# Stm32F411CEU6_Property.net
KiCad netlist of a schematic drawn in Altium Designer
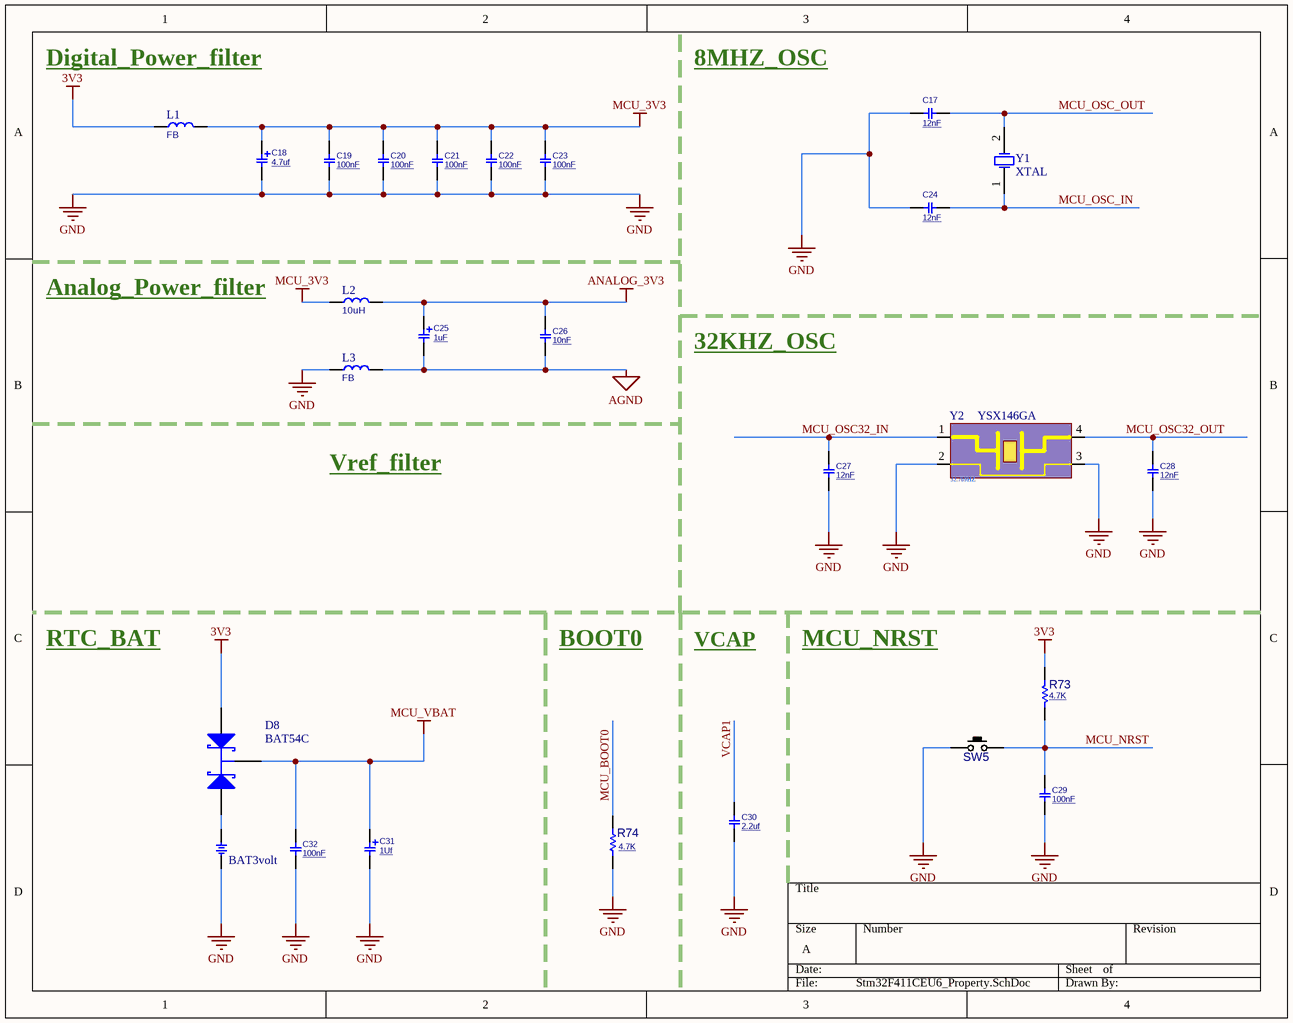
[diagram p0: Stm32F411CEU6_Property.SchDoc]

(export (version "E")
  (design (tool "Eeschema 10.0.6"))
  (components
    (comp (ref "BT1")
      (value "BAT3volt")
      (footprint "BTH1220")
      (description "BATTERY HOLDER, CR1220")
      (libsource (lib "battery") (part "BATH_CR1220"))
    )
    (comp (ref "C17")
      (value "12nF")
      (footprint "C0603")
      (description "CAP, MLCC, -F, -V, MATERIAL, -%, 0201")
      (fields (field (name "MANF_P#") "MANF_PART#"))
      (libsource (lib "passive_smd") (part "CAP_SMD_MLCC_0603"))
    )
    (comp (ref "C18")
      (value "4.7uf")
      (footprint "C_TN_3216")
      (description "CAP, SMD, TAN,")
      (fields (field (name "Comment") "4.7uF"))
      (libsource (lib "passive_smd") (part "CAP_SMD_TAN_3216"))
    )
    (comp (ref "C19")
      (value "100nF")
      (footprint "C0603")
      (description "CAP, MLCC, -F, -V, MATERIAL, -%, 0201")
      (fields (field (name "MANF_P#") "MANF_PART#"))
      (libsource (lib "passive_smd") (part "CAP_SMD_MLCC_0603"))
    )
    (comp (ref "C20")
      (value "100nF")
      (footprint "C0603")
      (description "CAP, MLCC, -F, -V, MATERIAL, -%, 0201")
      (fields (field (name "MANF_P#") "MANF_PART#"))
      (libsource (lib "passive_smd") (part "CAP_SMD_MLCC_0603"))
    )
    (comp (ref "C21")
      (value "100nF")
      (footprint "C0603")
      (description "CAP, MLCC, -F, -V, MATERIAL, -%, 0201")
      (fields (field (name "MANF_P#") "MANF_PART#"))
      (libsource (lib "passive_smd") (part "CAP_SMD_MLCC_0603"))
    )
    (comp (ref "C22")
      (value "100nF")
      (footprint "C0603")
      (description "CAP, MLCC, -F, -V, MATERIAL, -%, 0201")
      (fields (field (name "MANF_P#") "MANF_PART#"))
      (libsource (lib "passive_smd") (part "CAP_SMD_MLCC_0603"))
    )
    (comp (ref "C23")
      (value "100nF")
      (footprint "C0603")
      (description "CAP, MLCC, -F, -V, MATERIAL, -%, 0201")
      (fields (field (name "MANF_P#") "MANF_PART#"))
      (libsource (lib "passive_smd") (part "CAP_SMD_MLCC_0603"))
    )
    (comp (ref "C24")
      (value "12nF")
      (footprint "C0603")
      (description "CAP, MLCC, -F, -V, MATERIAL, -%, 0201")
      (fields (field (name "MANF_P#") "MANF_PART#"))
      (libsource (lib "passive_smd") (part "CAP_SMD_MLCC_0603"))
    )
    (comp (ref "C25")
      (value "1uF")
      (footprint "C_TN_3216")
      (description "CAP, SMD, TAN,")
      (fields (field (name "Comment") "4.7uF"))
      (libsource (lib "passive_smd") (part "CAP_SMD_TAN_3216"))
    )
    (comp (ref "C26")
      (value "10nF")
      (footprint "C0603")
      (description "CAP, MLCC, -F, -V, MATERIAL, -%, 0201")
      (fields (field (name "MANF_P#") "MANF_PART#"))
      (libsource (lib "passive_smd") (part "CAP_SMD_MLCC_0603"))
    )
    (comp (ref "C27")
      (value "12nF")
      (footprint "C0603")
      (description "CAP, MLCC, -F, -V, MATERIAL, -%, 0201")
      (fields (field (name "MANF_P#") "MANF_PART#"))
      (libsource (lib "passive_smd") (part "CAP_SMD_MLCC_0603"))
    )
    (comp (ref "C28")
      (value "12nF")
      (footprint "C0603")
      (description "CAP, MLCC, -F, -V, MATERIAL, -%, 0201")
      (fields (field (name "MANF_P#") "MANF_PART#"))
      (libsource (lib "passive_smd") (part "CAP_SMD_MLCC_0603"))
    )
    (comp (ref "C29")
      (value "100nF")
      (footprint "C0603")
      (description "CAP, MLCC, -F, -V, MATERIAL, -%, 0201")
      (fields (field (name "MANF_P#") "MANF_PART#"))
      (libsource (lib "passive_smd") (part "CAP_SMD_MLCC_0603"))
    )
    (comp (ref "C30")
      (value "2.2uf")
      (footprint "C0603")
      (description "CAP, MLCC, -F, -V, MATERIAL, -%, 0201")
      (fields (field (name "MANF_P#") "MANF_PART#"))
      (libsource (lib "passive_smd") (part "CAP_SMD_MLCC_0603"))
    )
    (comp (ref "C31")
      (value "1Uf")
      (footprint "C_TN_3216")
      (description "CAP, SMD, TAN,")
      (fields (field (name "Comment") "4.7uF"))
      (libsource (lib "passive_smd") (part "CAP_SMD_TAN_3216"))
    )
    (comp (ref "C32")
      (value "100nF")
      (footprint "C0603")
      (description "CAP, MLCC, -F, -V, MATERIAL, -%, 0201")
      (fields (field (name "MANF_P#") "MANF_PART#"))
      (libsource (lib "passive_smd") (part "CAP_SMD_MLCC_0603"))
    )
    (comp (ref "D8")
      (value "BAT54C")
      (footprint "NXP-SOT23-3_V")
      (description "Schottky Barrier Diode, 30 V, 2 uA, -55 to 150 degC, 3-Pin SOT23, RoHS, Tape and Reel")
      (fields (field (name "MANUFACTURER") "NXP Semiconductors"))
      (libsource (lib "BAT54C") (part "CMP-0417-00003-1"))
    )
    (comp (ref "L1")
      (value "FB")
      (footprint "L0805")
      (description "INDUCTOR, SMD")
      (libsource (lib "passive_smd") (part "IND_SMD"))
    )
    (comp (ref "L2")
      (value "10uH")
      (footprint "L1210A")
      (description "INDUCTOR, SMD")
      (libsource (lib "passive_smd") (part "IND_SMD"))
    )
    (comp (ref "L3")
      (value "FB")
      (footprint "L0805")
      (description "INDUCTOR, SMD")
      (libsource (lib "passive_smd") (part "IND_SMD"))
    )
    (comp (ref "R73")
      (value "4.7K")
      (footprint "R0603")
      (description "RESISTOR, SMD")
      (libsource (lib "passive_smd") (part "RES_SMD"))
    )
    (comp (ref "R74")
      (value "4.7K")
      (footprint "R0603")
      (description "RESISTOR, SMD")
      (libsource (lib "passive_smd") (part "RES_SMD"))
    )
    (comp (ref "SW5")
      (value "PUSHBUTTON")
      (footprint "SWPBS_SPST_6X3X5")
      (description "SWITCH, PUSH BUTTON, TACTILE, SMD, SPST, 6X3.5X5mm")
      (fields (field (name "MANF") "ALPS") (field (name "MANF_P#") "SKQMBBE010"))
      (libsource (lib "switch_tact_PUSHB") (part "SWPBS_SPST_6X3X5"))
    )
    (comp (ref "Y1")
      (value "XTAL")
      (footprint "XTL_2_5032")
      (description "Crystal Oscillator")
      (fields (field (name "PUBLISHER") "Altium Limited"))
      (libsource (lib "Miscellaneous Devices") (part "XTAL"))
    )
    (comp (ref "Y2")
      (value "YSX146GA")
      (footprint "YSX146GA-32.768xTAL")
      (libsource (lib "YSX146GA-32.768HZ") (part "YSX146GA"))
    )
  )
  (nets
    (net (code "1") (name "/MCU_BOOT0") (class "Default")
      (node (ref "R74") (pin "2") (pinfunction "2_2") (pintype "passive"))
    )
    (net (code "2") (name "/MCU_NRST") (class "Default")
      (node (ref "C29") (pin "2") (pinfunction "2_2") (pintype "passive"))
      (node (ref "R73") (pin "1") (pinfunction "1_1") (pintype "passive"))
      (node (ref "SW5") (pin "2") (pinfunction "P3_2") (pintype "passive"))
    )
    (net (code "3") (name "/MCU_OSC32_IN") (class "Default")
      (node (ref "C27") (pin "1") (pinfunction "1_1") (pintype "passive"))
      (node (ref "Y2") (pin "1") (pinfunction "1_1") (pintype "passive"))
    )
    (net (code "4") (name "/MCU_OSC32_OUT") (class "Default")
      (node (ref "C28") (pin "1") (pinfunction "1_1") (pintype "passive"))
      (node (ref "Y2") (pin "4") (pinfunction "4_4") (pintype "passive"))
    )
    (net (code "5") (name "/MCU_OSC_IN") (class "Default")
      (node (ref "C24") (pin "1") (pinfunction "1_1") (pintype "passive"))
      (node (ref "Y1") (pin "1") (pinfunction "OSC1_1") (pintype "passive"))
    )
    (net (code "6") (name "/MCU_OSC_OUT") (class "Default")
      (node (ref "C17") (pin "1") (pinfunction "1_1") (pintype "passive"))
      (node (ref "Y1") (pin "2") (pinfunction "OSC2_2") (pintype "passive"))
    )
    (net (code "7") (name "/VCAP1") (class "Default")
      (node (ref "C30") (pin "2") (pinfunction "2_2") (pintype "passive"))
    )
    (net (code "8") (name "3V3") (class "Default")
      (node (ref "D8") (pin "1") (pinfunction "A_1") (pintype "passive"))
      (node (ref "L1") (pin "1") (pinfunction "1_1") (pintype "passive"))
      (node (ref "R73") (pin "2") (pinfunction "2_2") (pintype "passive"))
    )
    (net (code "9") (name "AGND") (class "Default")
      (node (ref "C25") (pin "2") (pinfunction "2_2") (pintype "passive"))
      (node (ref "C26") (pin "1") (pinfunction "1_1") (pintype "passive"))
      (node (ref "L3") (pin "2") (pinfunction "2_2") (pintype "passive"))
    )
    (net (code "10") (name "ANALOG_3V3") (class "Default")
      (node (ref "C25") (pin "1") (pinfunction "1_1") (pintype "passive"))
      (node (ref "C26") (pin "2") (pinfunction "2_2") (pintype "passive"))
      (node (ref "L2") (pin "2") (pinfunction "2_2") (pintype "passive"))
    )
    (net (code "11") (name "GND") (class "Default")
      (node (ref "BT1") (pin "2") (pinfunction "2_2") (pintype "passive"))
      (node (ref "C17") (pin "2") (pinfunction "2_2") (pintype "passive"))
      (node (ref "C18") (pin "2") (pinfunction "2_2") (pintype "passive"))
      (node (ref "C19") (pin "1") (pinfunction "1_1") (pintype "passive"))
      (node (ref "C20") (pin "1") (pinfunction "1_1") (pintype "passive"))
      (node (ref "C21") (pin "1") (pinfunction "1_1") (pintype "passive"))
      (node (ref "C22") (pin "1") (pinfunction "1_1") (pintype "passive"))
      (node (ref "C23") (pin "1") (pinfunction "1_1") (pintype "passive"))
      (node (ref "C24") (pin "2") (pinfunction "2_2") (pintype "passive"))
      (node (ref "C27") (pin "2") (pinfunction "2_2") (pintype "passive"))
      (node (ref "C28") (pin "2") (pinfunction "2_2") (pintype "passive"))
      (node (ref "C29") (pin "1") (pinfunction "1_1") (pintype "passive"))
      (node (ref "C30") (pin "1") (pinfunction "1_1") (pintype "passive"))
      (node (ref "C31") (pin "2") (pinfunction "2_2") (pintype "passive"))
      (node (ref "C32") (pin "1") (pinfunction "1_1") (pintype "passive"))
      (node (ref "L3") (pin "1") (pinfunction "1_1") (pintype "passive"))
      (node (ref "R74") (pin "1") (pinfunction "1_1") (pintype "passive"))
      (node (ref "SW5") (pin "1") (pinfunction "P1_1") (pintype "passive"))
      (node (ref "Y2") (pin "2") (pinfunction "2_2") (pintype "passive"))
      (node (ref "Y2") (pin "3") (pinfunction "3_3") (pintype "passive"))
    )
    (net (code "12") (name "MCU_3V3") (class "Default")
      (node (ref "C18") (pin "1") (pinfunction "1_1") (pintype "passive"))
      (node (ref "C19") (pin "2") (pinfunction "2_2") (pintype "passive"))
      (node (ref "C20") (pin "2") (pinfunction "2_2") (pintype "passive"))
      (node (ref "C21") (pin "2") (pinfunction "2_2") (pintype "passive"))
      (node (ref "C22") (pin "2") (pinfunction "2_2") (pintype "passive"))
      (node (ref "C23") (pin "2") (pinfunction "2_2") (pintype "passive"))
      (node (ref "L1") (pin "2") (pinfunction "2_2") (pintype "passive"))
      (node (ref "L2") (pin "1") (pinfunction "1_1") (pintype "passive"))
    )
    (net (code "13") (name "MCU_VBAT") (class "Default")
      (node (ref "C31") (pin "1") (pinfunction "1_1") (pintype "passive"))
      (node (ref "C32") (pin "2") (pinfunction "2_2") (pintype "passive"))
      (node (ref "D8") (pin "3") (pinfunction "K_3") (pintype "passive"))
    )
    (net (code "14") (name "Net-(BT1-Pad1)") (class "Default")
      (node (ref "BT1") (pin "1") (pinfunction "1_1") (pintype "passive"))
      (node (ref "D8") (pin "2") (pinfunction "A_2") (pintype "passive"))
    )
  )
)
